# 03_-_POWER.net
KiCad netlist of a schematic drawn in Altium Designer
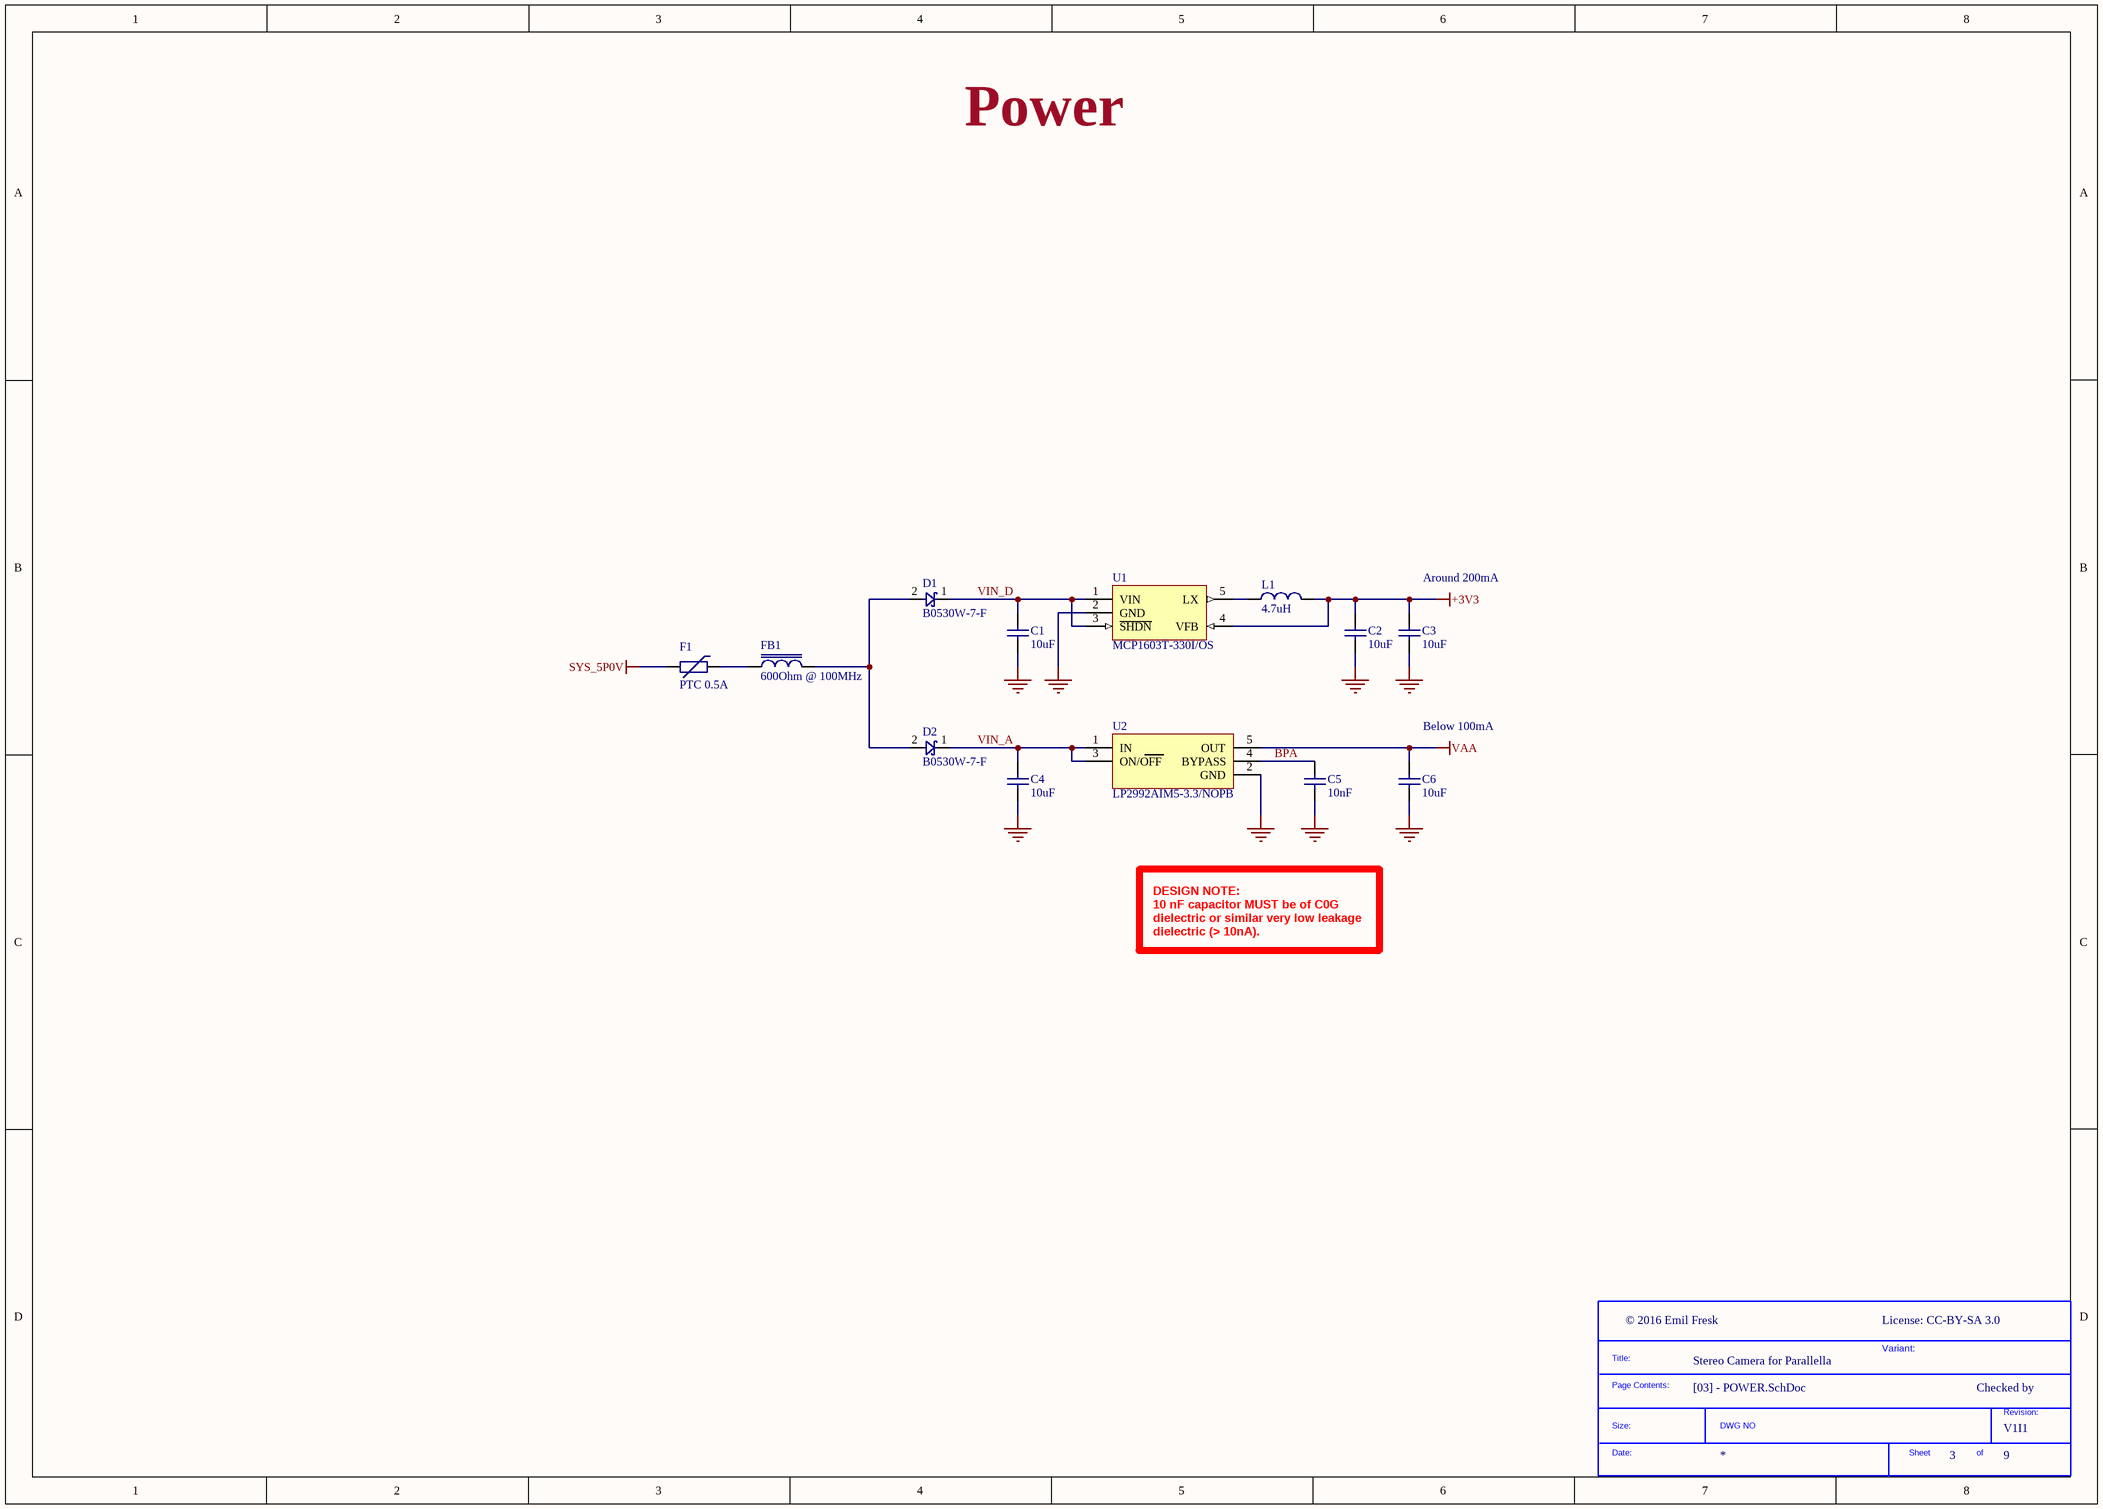
[diagram p0: [03] - POWER.SchDoc]

(export (version "E")
  (design (tool "Eeschema 10.0.6"))
  (components
    (comp (ref "C1")
      (value "10uF")
      (footprint "C0603L")
      (description "CAP CER 10UF 16V 20% X5R 0603")
      (fields
        (field (name "MANUFACTURER") "Murata Electronics North America")
        (field (name "MANUFACTURER PART NUMBER") "GRM188R61C106MA73D")
      )
      (libsource (lib "Capacitors") (part "GRM188R61C106MA73D"))
    )
    (comp (ref "C2")
      (value "10uF")
      (footprint "C0603L")
      (description "CAP CER 10UF 16V 20% X5R 0603")
      (fields
        (field (name "MANUFACTURER") "Murata Electronics North America")
        (field (name "MANUFACTURER PART NUMBER") "GRM188R61C106MA73D")
      )
      (libsource (lib "Capacitors") (part "GRM188R61C106MA73D"))
    )
    (comp (ref "C3")
      (value "10uF")
      (footprint "C0603L")
      (description "CAP CER 10UF 16V 20% X5R 0603")
      (fields
        (field (name "MANUFACTURER") "Murata Electronics North America")
        (field (name "MANUFACTURER PART NUMBER") "GRM188R61C106MA73D")
      )
      (libsource (lib "Capacitors") (part "GRM188R61C106MA73D"))
    )
    (comp (ref "C4")
      (value "10uF")
      (footprint "C0603L")
      (description "CAP CER 10UF 16V 20% X5R 0603")
      (fields
        (field (name "MANUFACTURER") "Murata Electronics North America")
        (field (name "MANUFACTURER PART NUMBER") "GRM188R61C106MA73D")
      )
      (libsource (lib "Capacitors") (part "GRM188R61C106MA73D"))
    )
    (comp (ref "C5")
      (value "10nF")
      (footprint "C0603L")
      (description "CAP CER 10000PF 25V 5% C0G 0603")
      (fields
        (field (name "MANUFACTURER") "TDK Corporation")
        (field (name "MANUFACTURER PART NUMBER") "C1608C0G1E103J080AA")
      )
      (libsource (lib "Capacitors") (part "C1608C0G1E103J080AA"))
    )
    (comp (ref "C6")
      (value "10uF")
      (footprint "C0603L")
      (description "CAP CER 10UF 16V 20% X5R 0603")
      (fields
        (field (name "MANUFACTURER") "Murata Electronics North America")
        (field (name "MANUFACTURER PART NUMBER") "GRM188R61C106MA73D")
      )
      (libsource (lib "Capacitors") (part "GRM188R61C106MA73D"))
    )
    (comp (ref "D1")
      (value "B0530W-7-F")
      (footprint "SOD123_DIODE")
      (description "DIODE SCHOTTKY 30V 500MA SOD123")
      (fields (field (name "MANUFACTURER") "Diodes Incorporated"))
      (libsource (lib "Diodes") (part "B0530W-7-F"))
    )
    (comp (ref "D2")
      (value "B0530W-7-F")
      (footprint "SOD123_DIODE")
      (description "DIODE SCHOTTKY 30V 500MA SOD123")
      (fields (field (name "MANUFACTURER") "Diodes Incorporated"))
      (libsource (lib "Diodes") (part "B0530W-7-F"))
    )
    (comp (ref "F1")
      (value "PTC 0.5A")
      (footprint "FUSE_1812")
      (description "PTC RESETTBLE 0.50A 30V CHIP 181")
      (fields
        (field (name "MANUFACTURER") "Bel Fuse Inc")
        (field (name "MANUFACTURER PART NUMBER") "0ZCG0050AF2C")
      )
      (libsource (lib "Fuses") (part "0ZCG0050AF2C"))
    )
    (comp (ref "FB1")
      (value "600Ohm @ 100MHz")
      (footprint "R0603L")
      (description "FERRITE CHIP BEAD 600 OHM SMD")
      (fields
        (field (name "MANUFACTURER") "TDK Corporation")
        (field (name "MANUFACTURER PART NUMBER") "MPZ1608S601ATA00")
      )
      (libsource (lib "Inductors") (part "MPZ1608S601ATA00"))
    )
    (comp (ref "L1")
      (value "4.7uH")
      (footprint "L_SRN3015")
      (description "FIXED IND 4.7UH 1.4A 136 MOHM")
      (fields
        (field (name "MANUFACTURER") "Bourns Inc.")
        (field (name "MANUFACTURER PART NUMBER") "SRN3015-4R7M")
      )
      (libsource (lib "Inductors") (part "SRN3015-4R7M"))
    )
    (comp (ref "U1")
      (value "MCP1603T-330I/OS")
      (footprint "SOT23-5N")
      (description "IC REG BCK 3.3V 0.5A SYNC TSOT23")
      (fields (field (name "MANUFACTURER") "Microchip Technology"))
      (libsource (lib "DCDC") (part "MCP1603T-330I/OS"))
    )
    (comp (ref "U2")
      (value "LP2992AIM5-3.3/NOPB")
      (footprint "SOT23-5N")
      (description "IC REG LDO 3.3V 0.25A SOT23-5")
      (fields (field (name "MANUFACTURER") "Texas Instruments"))
      (libsource (lib "LDOs") (part "LP2992AIM5-3.3/NOPB"))
    )
  )
  (nets
    (net (code "1") (name "+3V3") (class "Default")
      (node (ref "C2") (pin "1") (pinfunction "1_1") (pintype "passive"))
      (node (ref "C3") (pin "1") (pinfunction "1_1") (pintype "passive"))
      (node (ref "L1") (pin "2") (pinfunction "2_2") (pintype "passive"))
      (node (ref "U1") (pin "4") (pinfunction "VFB_4") (pintype "input"))
    )
    (net (code "2") (name "/BPA") (class "Default")
      (node (ref "C5") (pin "1") (pinfunction "1_1") (pintype "passive"))
      (node (ref "U2") (pin "4") (pinfunction "BYPASS_4") (pintype "passive"))
    )
    (net (code "3") (name "/VIN_A") (class "Default")
      (node (ref "C4") (pin "1") (pinfunction "1_1") (pintype "passive"))
      (node (ref "D2") (pin "1") (pinfunction "1_1") (pintype "passive"))
      (node (ref "U2") (pin "1") (pinfunction "IN_1") (pintype "passive"))
      (node (ref "U2") (pin "3") (pinfunction "ON/OFF_3") (pintype "passive"))
    )
    (net (code "4") (name "/VIN_D") (class "Default")
      (node (ref "C1") (pin "1") (pinfunction "1_1") (pintype "passive"))
      (node (ref "D1") (pin "1") (pinfunction "1_1") (pintype "passive"))
      (node (ref "U1") (pin "1") (pinfunction "VIN_1") (pintype "power_in"))
      (node (ref "U1") (pin "3") (pinfunction "~{SHDN}_3") (pintype "input"))
    )
    (net (code "5") (name "GND") (class "Default")
      (node (ref "C1") (pin "2") (pinfunction "2_2") (pintype "passive"))
      (node (ref "C2") (pin "2") (pinfunction "2_2") (pintype "passive"))
      (node (ref "C3") (pin "2") (pinfunction "2_2") (pintype "passive"))
      (node (ref "C4") (pin "2") (pinfunction "2_2") (pintype "passive"))
      (node (ref "C5") (pin "2") (pinfunction "2_2") (pintype "passive"))
      (node (ref "C6") (pin "2") (pinfunction "2_2") (pintype "passive"))
      (node (ref "U1") (pin "2") (pinfunction "GND_2") (pintype "power_in"))
      (node (ref "U2") (pin "2") (pinfunction "GND_2") (pintype "passive"))
    )
    (net (code "6") (name "Net-(D1-Pad2)") (class "Default")
      (node (ref "D1") (pin "2") (pinfunction "2_2") (pintype "passive"))
      (node (ref "D2") (pin "2") (pinfunction "2_2") (pintype "passive"))
      (node (ref "FB1") (pin "2") (pinfunction "2_2") (pintype "passive"))
    )
    (net (code "7") (name "Net-(F1-Pad2)") (class "Default")
      (node (ref "F1") (pin "2") (pinfunction "2_2") (pintype "passive"))
      (node (ref "FB1") (pin "1") (pinfunction "1_1") (pintype "passive"))
    )
    (net (code "8") (name "Net-(U1-LX)") (class "Default")
      (node (ref "L1") (pin "1") (pinfunction "1_1") (pintype "passive"))
      (node (ref "U1") (pin "5") (pinfunction "LX_5") (pintype "output"))
    )
    (net (code "9") (name "SYS_5P0V") (class "Default")
      (node (ref "F1") (pin "1") (pinfunction "1_1") (pintype "passive"))
    )
    (net (code "10") (name "VAA") (class "Default")
      (node (ref "C6") (pin "1") (pinfunction "1_1") (pintype "passive"))
      (node (ref "U2") (pin "5") (pinfunction "OUT_5") (pintype "passive"))
    )
  )
)
